# fms_controller.net
KiCad netlist of a schematic drawn in EAGLE
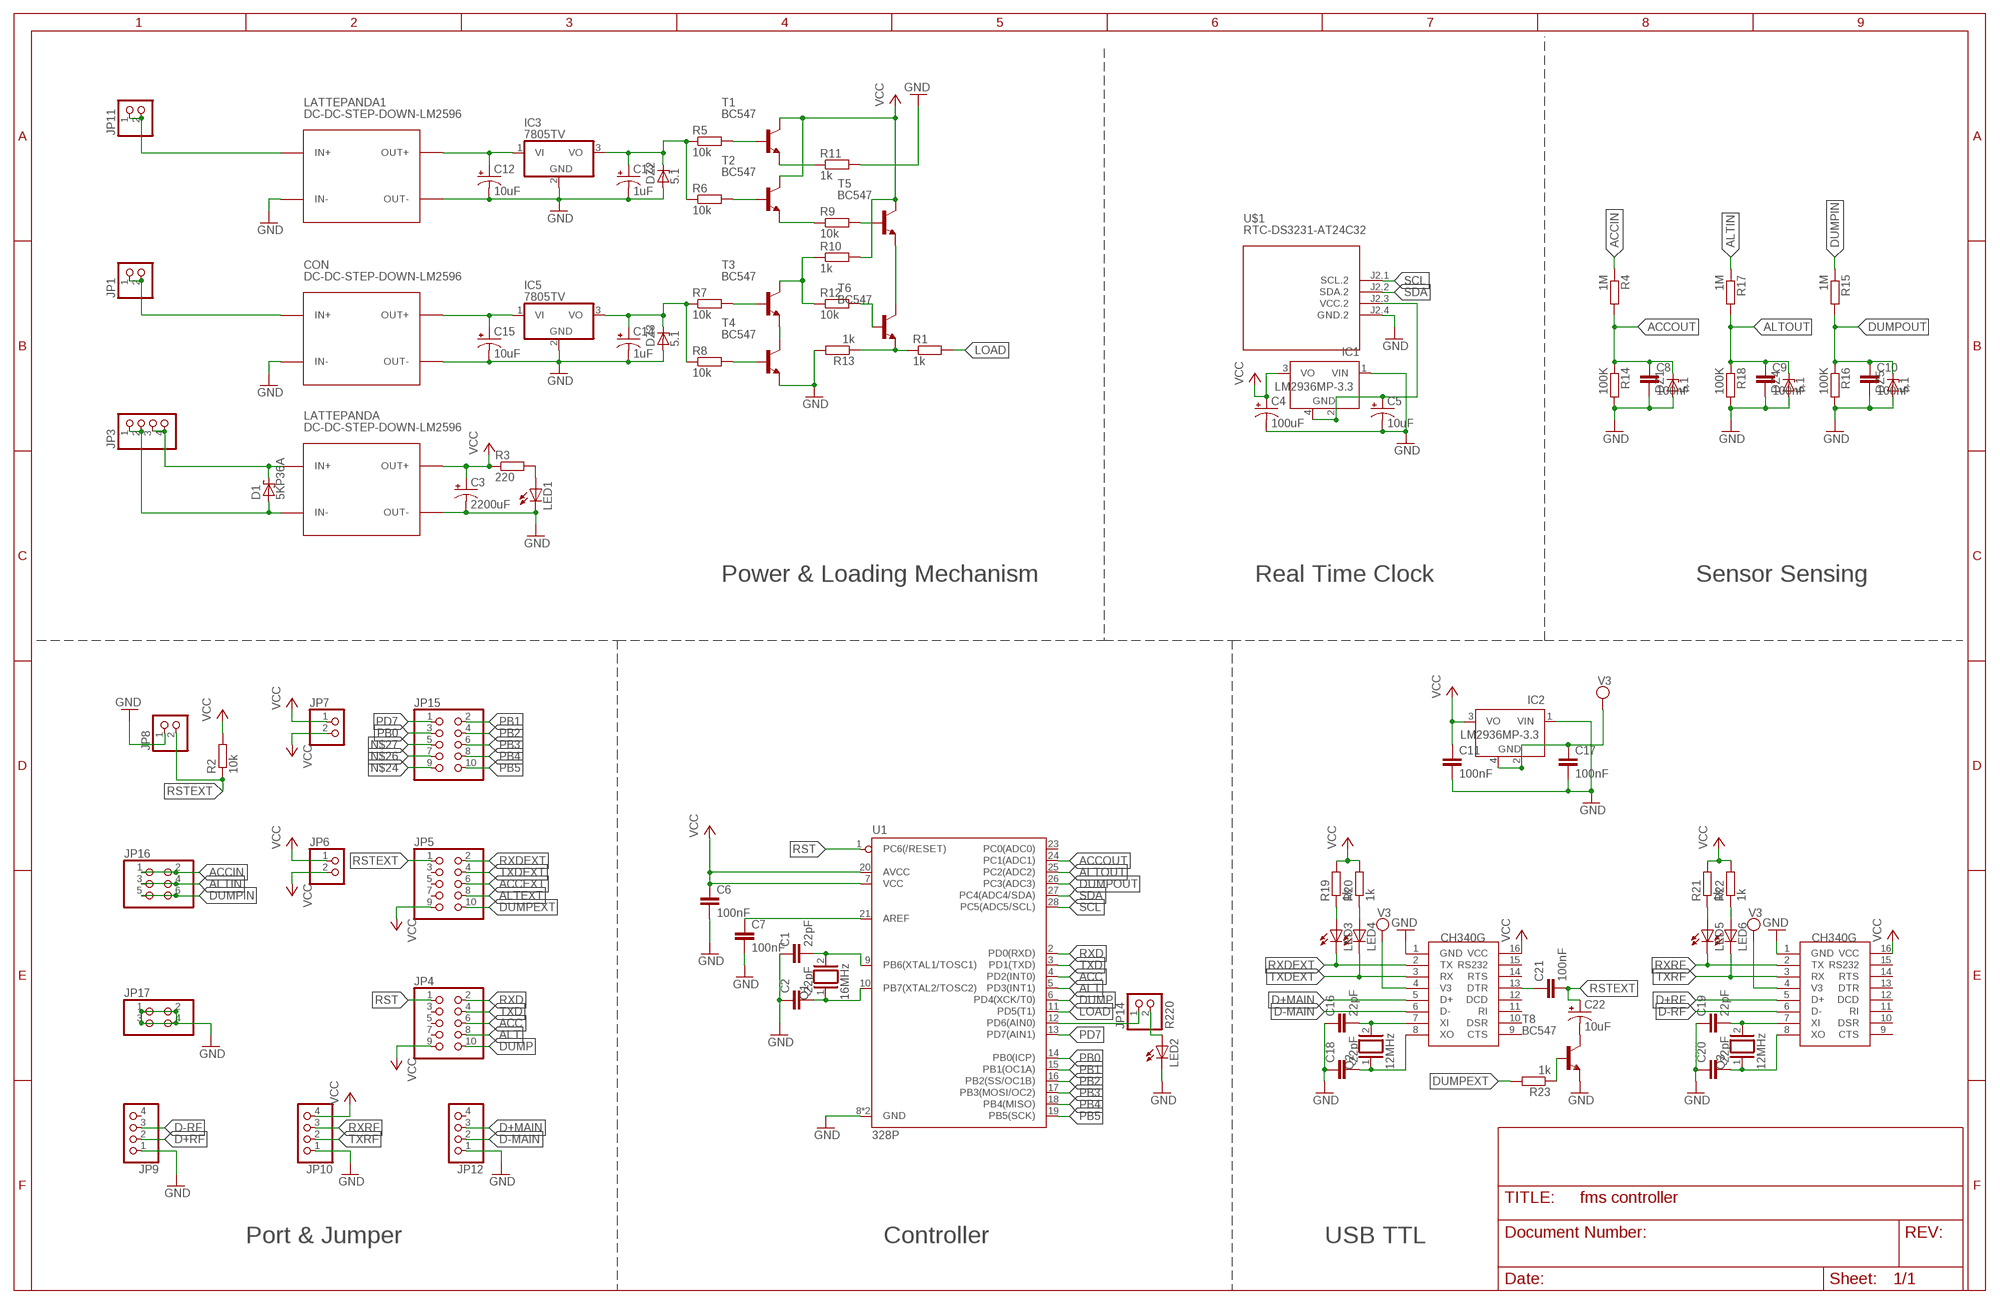
[diagram p0: schematic, sheet 1]

(export (version "E")
  (design (tool "Eeschema 10.0.6"))
  (components
    (comp (ref "C1")
      (value "22pF")
      (footprint "eagle-import:C2.5-3")
      (libsource (lib "eagle-import") (part "C2,5-3"))
    )
    (comp (ref "C2")
      (value "22pF")
      (footprint "eagle-import:C2.5-3")
      (libsource (lib "eagle-import") (part "C2,5-3"))
    )
    (comp (ref "C3")
      (value "2200uF")
      (footprint "eagle-import:E5-13")
      (libsource (lib "eagle-import") (part "CPOL-USE5-13"))
    )
    (comp (ref "C4")
      (value "100uF")
      (footprint "eagle-import:E2-5")
      (libsource (lib "eagle-import") (part "CPOL-USE2-5"))
    )
    (comp (ref "C5")
      (value "10uF")
      (footprint "eagle-import:E2-5")
      (libsource (lib "eagle-import") (part "CPOL-USE2-5"))
    )
    (comp (ref "C6")
      (value "100nF")
      (footprint "eagle-import:C025-040X050")
      (libsource (lib "eagle-import") (part "C-EU025-040X050"))
    )
    (comp (ref "C7")
      (value "100nF")
      (footprint "eagle-import:C025-040X050")
      (libsource (lib "eagle-import") (part "C-EU025-040X050"))
    )
    (comp (ref "C8")
      (value "100nF")
      (footprint "eagle-import:C025-040X050")
      (libsource (lib "eagle-import") (part "C-EU025-040X050"))
    )
    (comp (ref "C9")
      (value "100nF")
      (footprint "eagle-import:C025-040X050")
      (libsource (lib "eagle-import") (part "C-EU025-040X050"))
    )
    (comp (ref "C10")
      (value "100nF")
      (footprint "eagle-import:C025-040X050")
      (libsource (lib "eagle-import") (part "C-EU025-040X050"))
    )
    (comp (ref "C11")
      (value "100nF")
      (footprint "eagle-import:C025-040X050")
      (libsource (lib "eagle-import") (part "C-EU025-040X050"))
    )
    (comp (ref "C12")
      (value "10uF")
      (footprint "eagle-import:E2-5")
      (libsource (lib "eagle-import") (part "CPOL-USE2-5"))
    )
    (comp (ref "C13")
      (value "1uF")
      (footprint "eagle-import:E2-5")
      (libsource (lib "eagle-import") (part "CPOL-USE2-5"))
    )
    (comp (ref "C14")
      (value "1uF")
      (footprint "eagle-import:E2-5")
      (libsource (lib "eagle-import") (part "CPOL-USE2-5"))
    )
    (comp (ref "C15")
      (value "10uF")
      (footprint "eagle-import:E2-5")
      (libsource (lib "eagle-import") (part "CPOL-USE2-5"))
    )
    (comp (ref "C16")
      (value "22pF")
      (footprint "eagle-import:C2.5-3")
      (libsource (lib "eagle-import") (part "C2,5-3"))
    )
    (comp (ref "C17")
      (value "100nF")
      (footprint "eagle-import:C025-040X050")
      (libsource (lib "eagle-import") (part "C-EU025-040X050"))
    )
    (comp (ref "C18")
      (value "22pF")
      (footprint "eagle-import:C2.5-3")
      (libsource (lib "eagle-import") (part "C2,5-3"))
    )
    (comp (ref "C19")
      (value "22pF")
      (footprint "eagle-import:C2.5-3")
      (libsource (lib "eagle-import") (part "C2,5-3"))
    )
    (comp (ref "C20")
      (value "22pF")
      (footprint "eagle-import:C2.5-3")
      (libsource (lib "eagle-import") (part "C2,5-3"))
    )
    (comp (ref "C21")
      (value "100nF")
      (footprint "eagle-import:C025-040X050")
      (libsource (lib "eagle-import") (part "C-EU025-040X050"))
    )
    (comp (ref "C22")
      (value "10uF")
      (footprint "eagle-import:E2-5")
      (libsource (lib "eagle-import") (part "CPOL-USE2-5"))
    )
    (comp (ref "CON")
      (value "DC-DC-STEP-DOWN-LM2596")
      (footprint "eagle-import:DC-DC-STEP-DOWN-LM2596")
      (libsource (lib "eagle-import") (part "DC-DC-STEP-DOWN-LM2596"))
    )
    (comp (ref "D1")
      (value "5KP36A")
      (footprint "eagle-import:P6T15")
      (libsource (lib "eagle-import") (part "5KPXX"))
    )
    (comp (ref "DZ1")
      (value "5.1")
      (footprint "eagle-import:DO35Z10")
      (libsource (lib "eagle-import") (part "ZPD"))
    )
    (comp (ref "DZ2")
      (value "5.1")
      (footprint "eagle-import:DO35Z10")
      (libsource (lib "eagle-import") (part "ZPD"))
    )
    (comp (ref "DZ3")
      (value "5.1")
      (footprint "eagle-import:DO35Z10")
      (libsource (lib "eagle-import") (part "ZPD"))
    )
    (comp (ref "DZ4")
      (value "5.1")
      (footprint "eagle-import:DO35Z10")
      (libsource (lib "eagle-import") (part "ZPD"))
    )
    (comp (ref "DZ5")
      (value "5.1")
      (footprint "eagle-import:DO35Z10")
      (libsource (lib "eagle-import") (part "ZPD"))
    )
    (comp (ref "IC1")
      (value "LM2936MP-3.3")
      (footprint "eagle-import:SOT223")
      (fields (field (name "MF") "NATIONAL SEMICONDUCTOR") (field (name "MPN") "LM2936MP-3.3/NOPB"))
      (libsource (lib "eagle-import") (part "LM2936MP?-3.3"))
    )
    (comp (ref "IC2")
      (value "LM2936MP-3.3")
      (footprint "eagle-import:SOT223")
      (fields (field (name "MF") "NATIONAL SEMICONDUCTOR") (field (name "MPN") "LM2936MP-3.3/NOPB"))
      (libsource (lib "eagle-import") (part "LM2936MP?-3.3"))
    )
    (comp (ref "IC3")
      (value "7805TV")
      (footprint "eagle-import:TO220V")
      (libsource (lib "eagle-import") (part "78TV05"))
    )
    (comp (ref "IC5")
      (value "7805TV")
      (footprint "eagle-import:TO220V")
      (libsource (lib "eagle-import") (part "78TV05"))
    )
    (comp (ref "JP1")
      (value "PINHD-1X2")
      (footprint "eagle-import:1X02")
      (libsource (lib "eagle-import") (part "PINHD-1X2"))
    )
    (comp (ref "JP3")
      (value "PINHD-1X4")
      (footprint "eagle-import:1X04")
      (libsource (lib "eagle-import") (part "PINHD-1X4"))
    )
    (comp (ref "JP4")
      (value "PINHD-2X5")
      (footprint "eagle-import:2X05")
      (libsource (lib "eagle-import") (part "PINHD-2X5"))
    )
    (comp (ref "JP5")
      (value "PINHD-2X5")
      (footprint "eagle-import:2X05")
      (libsource (lib "eagle-import") (part "PINHD-2X5"))
    )
    (comp (ref "JP6")
      (value "PINHD-1X2")
      (footprint "eagle-import:1X02")
      (libsource (lib "eagle-import") (part "PINHD-1X2"))
    )
    (comp (ref "JP7")
      (value "PINHD-1X2")
      (footprint "eagle-import:1X02")
      (libsource (lib "eagle-import") (part "PINHD-1X2"))
    )
    (comp (ref "JP8")
      (value "PINHD-1X2")
      (footprint "eagle-import:1X02")
      (libsource (lib "eagle-import") (part "PINHD-1X2"))
    )
    (comp (ref "JP9")
      (value "PINHD-1X4")
      (footprint "eagle-import:1X04")
      (libsource (lib "eagle-import") (part "PINHD-1X4"))
    )
    (comp (ref "JP10")
      (value "PINHD-1X4")
      (footprint "eagle-import:1X04")
      (libsource (lib "eagle-import") (part "PINHD-1X4"))
    )
    (comp (ref "JP11")
      (value "PINHD-1X2")
      (footprint "eagle-import:1X02")
      (libsource (lib "eagle-import") (part "PINHD-1X2"))
    )
    (comp (ref "JP12")
      (value "PINHD-1X4")
      (footprint "eagle-import:1X04")
      (libsource (lib "eagle-import") (part "PINHD-1X4"))
    )
    (comp (ref "JP14")
      (value "R220")
      (footprint "eagle-import:1X02")
      (libsource (lib "eagle-import") (part "PINHD-1X2"))
    )
    (comp (ref "JP15")
      (value "PINHD-2X5")
      (footprint "eagle-import:2X05")
      (libsource (lib "eagle-import") (part "PINHD-2X5"))
    )
    (comp (ref "JP16")
      (value "PINHD-2X3")
      (footprint "eagle-import:2X03")
      (libsource (lib "eagle-import") (part "PINHD-2X3"))
    )
    (comp (ref "JP17")
      (value "PINHD-2X2")
      (footprint "eagle-import:2X02")
      (libsource (lib "eagle-import") (part "PINHD-2X2"))
    )
    (comp (ref "LATTEPANDA")
      (value "DC-DC-STEP-DOWN-LM2596")
      (footprint "eagle-import:DC-DC-STEP-DOWN-LM2596")
      (libsource (lib "eagle-import") (part "DC-DC-STEP-DOWN-LM2596"))
    )
    (comp (ref "LATTEPANDA1")
      (value "DC-DC-STEP-DOWN-LM2596")
      (footprint "eagle-import:DC-DC-STEP-DOWN-LM2596")
      (libsource (lib "eagle-import") (part "DC-DC-STEP-DOWN-LM2596"))
    )
    (comp (ref "LED1")
      (value "LED3MM")
      (footprint "eagle-import:LED3MM")
      (libsource (lib "eagle-import") (part "LED3MM"))
    )
    (comp (ref "LED2")
      (value "LED3MM")
      (footprint "eagle-import:LED3MM")
      (libsource (lib "eagle-import") (part "LED3MM"))
    )
    (comp (ref "LED3")
      (value "LED3MM")
      (footprint "eagle-import:LED3MM")
      (libsource (lib "eagle-import") (part "LED3MM"))
    )
    (comp (ref "LED4")
      (value "LED3MM")
      (footprint "eagle-import:LED3MM")
      (libsource (lib "eagle-import") (part "LED3MM"))
    )
    (comp (ref "LED5")
      (value "LED3MM")
      (footprint "eagle-import:LED3MM")
      (libsource (lib "eagle-import") (part "LED3MM"))
    )
    (comp (ref "LED6")
      (value "LED3MM")
      (footprint "eagle-import:LED3MM")
      (libsource (lib "eagle-import") (part "LED3MM"))
    )
    (comp (ref "Q1")
      (value "16MHz")
      (footprint "eagle-import:QS")
      (libsource (lib "eagle-import") (part "XTAL/S"))
    )
    (comp (ref "Q2")
      (value "12MHz")
      (footprint "eagle-import:QS")
      (libsource (lib "eagle-import") (part "XTAL/S"))
    )
    (comp (ref "Q3")
      (value "12MHz")
      (footprint "eagle-import:QS")
      (libsource (lib "eagle-import") (part "XTAL/S"))
    )
    (comp (ref "R1")
      (value "1k")
      (footprint "eagle-import:0309_10")
      (libsource (lib "eagle-import") (part "R-EU_0309/10"))
    )
    (comp (ref "R2")
      (value "10k")
      (footprint "eagle-import:0309_10")
      (libsource (lib "eagle-import") (part "R-EU_0309/10"))
    )
    (comp (ref "R3")
      (value "220")
      (footprint "eagle-import:0309_10")
      (libsource (lib "eagle-import") (part "R-EU_0309/10"))
    )
    (comp (ref "R4")
      (value "1M")
      (footprint "eagle-import:0309_10")
      (libsource (lib "eagle-import") (part "R-EU_0309/10"))
    )
    (comp (ref "R5")
      (value "10k")
      (footprint "eagle-import:0309_10")
      (libsource (lib "eagle-import") (part "R-EU_0309/10"))
    )
    (comp (ref "R6")
      (value "10k")
      (footprint "eagle-import:0309_10")
      (libsource (lib "eagle-import") (part "R-EU_0309/10"))
    )
    (comp (ref "R7")
      (value "10k")
      (footprint "eagle-import:0309_10")
      (libsource (lib "eagle-import") (part "R-EU_0309/10"))
    )
    (comp (ref "R8")
      (value "10k")
      (footprint "eagle-import:0309_10")
      (libsource (lib "eagle-import") (part "R-EU_0309/10"))
    )
    (comp (ref "R9")
      (value "10k")
      (footprint "eagle-import:0309_10")
      (libsource (lib "eagle-import") (part "R-EU_0309/10"))
    )
    (comp (ref "R10")
      (value "1k")
      (footprint "eagle-import:0309_10")
      (libsource (lib "eagle-import") (part "R-EU_0309/10"))
    )
    (comp (ref "R11")
      (value "1k")
      (footprint "eagle-import:0309_10")
      (libsource (lib "eagle-import") (part "R-EU_0309/10"))
    )
    (comp (ref "R12")
      (value "10k")
      (footprint "eagle-import:0309_10")
      (libsource (lib "eagle-import") (part "R-EU_0309/10"))
    )
    (comp (ref "R13")
      (value "1k")
      (footprint "eagle-import:0309_10")
      (libsource (lib "eagle-import") (part "R-EU_0309/10"))
    )
    (comp (ref "R14")
      (value "100K")
      (footprint "eagle-import:0309_10")
      (libsource (lib "eagle-import") (part "R-EU_0309/10"))
    )
    (comp (ref "R15")
      (value "1M")
      (footprint "eagle-import:0309_10")
      (libsource (lib "eagle-import") (part "R-EU_0309/10"))
    )
    (comp (ref "R16")
      (value "100K")
      (footprint "eagle-import:0309_10")
      (libsource (lib "eagle-import") (part "R-EU_0309/10"))
    )
    (comp (ref "R17")
      (value "1M")
      (footprint "eagle-import:0309_10")
      (libsource (lib "eagle-import") (part "R-EU_0309/10"))
    )
    (comp (ref "R18")
      (value "100K")
      (footprint "eagle-import:0309_10")
      (libsource (lib "eagle-import") (part "R-EU_0309/10"))
    )
    (comp (ref "R19")
      (value "1k")
      (footprint "eagle-import:0309_10")
      (libsource (lib "eagle-import") (part "R-EU_0309/10"))
    )
    (comp (ref "R20")
      (value "1k")
      (footprint "eagle-import:0309_10")
      (libsource (lib "eagle-import") (part "R-EU_0309/10"))
    )
    (comp (ref "R21")
      (value "1k")
      (footprint "eagle-import:0309_10")
      (libsource (lib "eagle-import") (part "R-EU_0309/10"))
    )
    (comp (ref "R22")
      (value "1k")
      (footprint "eagle-import:0309_10")
      (libsource (lib "eagle-import") (part "R-EU_0309/10"))
    )
    (comp (ref "R23")
      (value "1k")
      (footprint "eagle-import:0309_10")
      (libsource (lib "eagle-import") (part "R-EU_0309/10"))
    )
    (comp (ref "T1")
      (value "BC547")
      (footprint "eagle-import:TO92")
      (libsource (lib "eagle-import") (part "BC547"))
    )
    (comp (ref "T2")
      (value "BC547")
      (footprint "eagle-import:TO92")
      (libsource (lib "eagle-import") (part "BC547"))
    )
    (comp (ref "T3")
      (value "BC547")
      (footprint "eagle-import:TO92")
      (libsource (lib "eagle-import") (part "BC547"))
    )
    (comp (ref "T4")
      (value "BC547")
      (footprint "eagle-import:TO92")
      (libsource (lib "eagle-import") (part "BC547"))
    )
    (comp (ref "T5")
      (value "BC547")
      (footprint "eagle-import:TO92")
      (libsource (lib "eagle-import") (part "BC547"))
    )
    (comp (ref "T6")
      (value "BC547")
      (footprint "eagle-import:TO92")
      (libsource (lib "eagle-import") (part "BC547"))
    )
    (comp (ref "T8")
      (value "BC547")
      (footprint "eagle-import:TO92")
      (libsource (lib "eagle-import") (part "BC547"))
    )
    (comp (ref "U$1")
      (value "RTC-DS3231-AT24C32")
      (footprint "eagle-import:RTC-DS3231-AT24C32")
      (libsource (lib "eagle-import") (part "RTC-DS3231-AT24C32"))
    )
    (comp (ref "U$2")
      (value "CH340G")
      (footprint "eagle-import:SOIC16")
      (libsource (lib "eagle-import") (part "CH340G"))
    )
    (comp (ref "U$3")
      (value "CH340G")
      (footprint "eagle-import:SOIC16")
      (libsource (lib "eagle-import") (part "CH340G"))
    )
    (comp (ref "U1")
      (value "328P")
      (footprint "eagle-import:DIP28")
      (libsource (lib "eagle-import") (part "ATMEGA328P_PDIP"))
    )
  )
  (nets
    (net (code "1") (name "ACC") (class "Default")
      (node (ref "JP4") (pin "6") (pinfunction "6_6") (pintype "passive"))
      (node (ref "U1") (pin "4") (pinfunction "PD2(INT0)_4") (pintype "bidirectional"))
    )
    (net (code "2") (name "ACCEXT") (class "Default")
      (node (ref "JP5") (pin "6") (pinfunction "6_6") (pintype "passive"))
    )
    (net (code "3") (name "ACCIN") (class "Default")
      (node (ref "JP16") (pin "1") (pinfunction "1_1") (pintype "passive"))
      (node (ref "JP16") (pin "2") (pinfunction "2_2") (pintype "passive"))
      (node (ref "R4") (pin "1") (pinfunction "1_1") (pintype "passive"))
    )
    (net (code "4") (name "ACCOUT") (class "Default")
      (node (ref "C8") (pin "1") (pinfunction "1_1") (pintype "passive"))
      (node (ref "DZ1") (pin "C") (pinfunction "C_C") (pintype "passive"))
      (node (ref "R14") (pin "1") (pinfunction "1_1") (pintype "passive"))
      (node (ref "R4") (pin "2") (pinfunction "2_2") (pintype "passive"))
      (node (ref "U1") (pin "24") (pinfunction "PC1(ADC1)_24") (pintype "bidirectional"))
    )
    (net (code "5") (name "ALT") (class "Default")
      (node (ref "JP4") (pin "8") (pinfunction "8_8") (pintype "passive"))
      (node (ref "U1") (pin "5") (pinfunction "PD3(INT1)_5") (pintype "bidirectional"))
    )
    (net (code "6") (name "ALTEXT") (class "Default")
      (node (ref "JP5") (pin "8") (pinfunction "8_8") (pintype "passive"))
    )
    (net (code "7") (name "ALTIN") (class "Default")
      (node (ref "JP16") (pin "3") (pinfunction "3_3") (pintype "passive"))
      (node (ref "JP16") (pin "4") (pinfunction "4_4") (pintype "passive"))
      (node (ref "R17") (pin "1") (pinfunction "1_1") (pintype "passive"))
    )
    (net (code "8") (name "ALTOUT") (class "Default")
      (node (ref "C9") (pin "1") (pinfunction "1_1") (pintype "passive"))
      (node (ref "DZ4") (pin "C") (pinfunction "C_C") (pintype "passive"))
      (node (ref "R17") (pin "2") (pinfunction "2_2") (pintype "passive"))
      (node (ref "R18") (pin "1") (pinfunction "1_1") (pintype "passive"))
      (node (ref "U1") (pin "25") (pinfunction "PC2(ADC2)_25") (pintype "bidirectional"))
    )
    (net (code "9") (name "D+MAIN") (class "Default")
      (node (ref "JP12") (pin "3") (pinfunction "3_3") (pintype "passive"))
      (node (ref "U$2") (pin "5") (pinfunction "D+_5") (pintype "bidirectional"))
    )
    (net (code "10") (name "D+RF") (class "Default")
      (node (ref "JP9") (pin "2") (pinfunction "2_2") (pintype "passive"))
      (node (ref "U$3") (pin "5") (pinfunction "D+_5") (pintype "bidirectional"))
    )
    (net (code "11") (name "D-MAIN") (class "Default")
      (node (ref "JP12") (pin "2") (pinfunction "2_2") (pintype "passive"))
      (node (ref "U$2") (pin "6") (pinfunction "D-_6") (pintype "bidirectional"))
    )
    (net (code "12") (name "D-RF") (class "Default")
      (node (ref "JP9") (pin "3") (pinfunction "3_3") (pintype "passive"))
      (node (ref "U$3") (pin "6") (pinfunction "D-_6") (pintype "bidirectional"))
    )
    (net (code "13") (name "DUMP") (class "Default")
      (node (ref "JP4") (pin "10") (pinfunction "10_10") (pintype "passive"))
      (node (ref "U1") (pin "6") (pinfunction "PD4(XCK/T0)_6") (pintype "bidirectional"))
    )
    (net (code "14") (name "DUMPEXT") (class "Default")
      (node (ref "JP5") (pin "10") (pinfunction "10_10") (pintype "passive"))
      (node (ref "R23") (pin "2") (pinfunction "2_2") (pintype "passive"))
    )
    (net (code "15") (name "DUMPIN") (class "Default")
      (node (ref "JP16") (pin "5") (pinfunction "5_5") (pintype "passive"))
      (node (ref "JP16") (pin "6") (pinfunction "6_6") (pintype "passive"))
      (node (ref "R15") (pin "1") (pinfunction "1_1") (pintype "passive"))
    )
    (net (code "16") (name "DUMPOUT") (class "Default")
      (node (ref "C10") (pin "1") (pinfunction "1_1") (pintype "passive"))
      (node (ref "DZ5") (pin "C") (pinfunction "C_C") (pintype "passive"))
      (node (ref "R15") (pin "2") (pinfunction "2_2") (pintype "passive"))
      (node (ref "R16") (pin "1") (pinfunction "1_1") (pintype "passive"))
      (node (ref "U1") (pin "26") (pinfunction "PC3(ADC3)_26") (pintype "bidirectional"))
    )
    (net (code "17") (name "GND") (class "Default")
      (node (ref "C1") (pin "1") (pinfunction "1_1") (pintype "passive"))
      (node (ref "C10") (pin "2") (pinfunction "2_2") (pintype "passive"))
      (node (ref "C11") (pin "2") (pinfunction "2_2") (pintype "passive"))
      (node (ref "C12") (pin "-") (pinfunction "-_-") (pintype "passive"))
      (node (ref "C13") (pin "-") (pinfunction "-_-") (pintype "passive"))
      (node (ref "C14") (pin "-") (pinfunction "-_-") (pintype "passive"))
      (node (ref "C15") (pin "-") (pinfunction "-_-") (pintype "passive"))
      (node (ref "C16") (pin "1") (pinfunction "1_1") (pintype "passive"))
      (node (ref "C17") (pin "2") (pinfunction "2_2") (pintype "passive"))
      (node (ref "C18") (pin "1") (pinfunction "1_1") (pintype "passive"))
      (node (ref "C19") (pin "1") (pinfunction "1_1") (pintype "passive"))
      (node (ref "C2") (pin "1") (pinfunction "1_1") (pintype "passive"))
      (node (ref "C20") (pin "1") (pinfunction "1_1") (pintype "passive"))
      (node (ref "C3") (pin "-") (pinfunction "-_-") (pintype "passive"))
      (node (ref "C4") (pin "-") (pinfunction "-_-") (pintype "passive"))
      (node (ref "C5") (pin "-") (pinfunction "-_-") (pintype "passive"))
      (node (ref "C6") (pin "2") (pinfunction "2_2") (pintype "passive"))
      (node (ref "C7") (pin "2") (pinfunction "2_2") (pintype "passive"))
      (node (ref "C8") (pin "2") (pinfunction "2_2") (pintype "passive"))
      (node (ref "C9") (pin "2") (pinfunction "2_2") (pintype "passive"))
      (node (ref "CON") (pin "IN-") (pinfunction "IN-_IN-") (pintype "bidirectional"))
      (node (ref "CON") (pin "OUT-") (pinfunction "OUT-_OUT-") (pintype "bidirectional"))
      (node (ref "DZ1") (pin "A") (pinfunction "A_A") (pintype "passive"))
      (node (ref "DZ2") (pin "A") (pinfunction "A_A") (pintype "passive"))
      (node (ref "DZ3") (pin "A") (pinfunction "A_A") (pintype "passive"))
      (node (ref "DZ4") (pin "A") (pinfunction "A_A") (pintype "passive"))
      (node (ref "DZ5") (pin "A") (pinfunction "A_A") (pintype "passive"))
      (node (ref "IC1") (pin "1") (pinfunction "VIN_1") (pintype "input"))
      (node (ref "IC2") (pin "1") (pinfunction "VIN_1") (pintype "input"))
      (node (ref "IC3") (pin "2") (pinfunction "GND_2") (pintype "passive"))
      (node (ref "IC5") (pin "2") (pinfunction "GND_2") (pintype "passive"))
      (node (ref "JP10") (pin "1") (pinfunction "1_1") (pintype "passive"))
      (node (ref "JP12") (pin "1") (pinfunction "1_1") (pintype "passive"))
      (node (ref "JP17") (pin "1") (pinfunction "1_1") (pintype "passive"))
      (node (ref "JP17") (pin "2") (pinfunction "2_2") (pintype "passive"))
      (node (ref "JP17") (pin "3") (pinfunction "3_3") (pintype "passive"))
      (node (ref "JP17") (pin "4") (pinfunction "4_4") (pintype "passive"))
      (node (ref "JP8") (pin "1") (pinfunction "1_1") (pintype "passive"))
      (node (ref "JP9") (pin "1") (pinfunction "1_1") (pintype "passive"))
      (node (ref "LATTEPANDA") (pin "OUT-") (pinfunction "OUT-_OUT-") (pintype "bidirectional"))
      (node (ref "LATTEPANDA1") (pin "IN-") (pinfunction "IN-_IN-") (pintype "bidirectional"))
      (node (ref "LATTEPANDA1") (pin "OUT-") (pinfunction "OUT-_OUT-") (pintype "bidirectional"))
      (node (ref "LED1") (pin "K") (pinfunction "C_K") (pintype "passive"))
      (node (ref "LED2") (pin "K") (pinfunction "C_K") (pintype "passive"))
      (node (ref "R11") (pin "2") (pinfunction "2_2") (pintype "passive"))
      (node (ref "R13") (pin "2") (pinfunction "2_2") (pintype "passive"))
      (node (ref "R14") (pin "2") (pinfunction "2_2") (pintype "passive"))
      (node (ref "R16") (pin "2") (pinfunction "2_2") (pintype "passive"))
      (node (ref "R18") (pin "2") (pinfunction "2_2") (pintype "passive"))
      (node (ref "T4") (pin "1") (pinfunction "E_1") (pintype "passive"))
      (node (ref "T8") (pin "1") (pinfunction "E_1") (pintype "passive"))
      (node (ref "U$1") (pin "J2.4") (pinfunction "GND.2_J2.4") (pintype "power_in"))
      (node (ref "U$2") (pin "1") (pinfunction "GND_1") (pintype "bidirectional"))
      (node (ref "U$3") (pin "1") (pinfunction "GND_1") (pintype "bidirectional"))
      (node (ref "U1") (pin "22") (pinfunction "GND_22") (pintype "bidirectional"))
      (node (ref "U1") (pin "8") (pinfunction "GND_8") (pintype "bidirectional"))
    )
    (net (code "18") (name "LOAD") (class "Default")
      (node (ref "R1") (pin "2") (pinfunction "2_2") (pintype "passive"))
      (node (ref "U1") (pin "11") (pinfunction "PD5(T1)_11") (pintype "bidirectional"))
    )
    (net (code "19") (name "N$24") (class "Default")
      (node (ref "JP15") (pin "9") (pinfunction "9_9") (pintype "passive"))
    )
    (net (code "20") (name "N$26") (class "Default")
      (node (ref "JP15") (pin "7") (pinfunction "7_7") (pintype "passive"))
    )
    (net (code "21") (name "N$27") (class "Default")
      (node (ref "JP15") (pin "5") (pinfunction "5_5") (pintype "passive"))
    )
    (net (code "22") (name "Net-(CON-PadIN+)") (class "Default")
      (node (ref "CON") (pin "IN+") (pinfunction "IN+_IN+") (pintype "bidirectional"))
      (node (ref "JP1") (pin "1") (pinfunction "1_1") (pintype "passive"))
      (node (ref "JP1") (pin "2") (pinfunction "2_2") (pintype "passive"))
    )
    (net (code "23") (name "Net-(D1-PadA)") (class "Default")
      (node (ref "D1") (pin "A") (pinfunction "A_A") (pintype "passive"))
      (node (ref "JP3") (pin "1") (pinfunction "1_1") (pintype "passive"))
      (node (ref "JP3") (pin "2") (pinfunction "2_2") (pintype "passive"))
      (node (ref "LATTEPANDA") (pin "IN-") (pinfunction "IN-_IN-") (pintype "bidirectional"))
    )
    (net (code "24") (name "Net-(D1-PadC)") (class "Default")
      (node (ref "D1") (pin "C") (pinfunction "C_C") (pintype "passive"))
      (node (ref "JP3") (pin "3") (pinfunction "3_3") (pintype "passive"))
      (node (ref "JP3") (pin "4") (pinfunction "4_4") (pintype "passive"))
      (node (ref "LATTEPANDA") (pin "IN+") (pinfunction "IN+_IN+") (pintype "bidirectional"))
    )
    (net (code "25") (name "Net-(IC3-VI)") (class "Default")
      (node (ref "C12") (pin "+") (pinfunction "+_+") (pintype "passive"))
      (node (ref "IC3") (pin "1") (pinfunction "VI_1") (pintype "input"))
      (node (ref "LATTEPANDA1") (pin "OUT+") (pinfunction "OUT+_OUT+") (pintype "bidirectional"))
    )
    (net (code "26") (name "Net-(IC3-VO)") (class "Default")
      (node (ref "C13") (pin "+") (pinfunction "+_+") (pintype "passive"))
      (node (ref "DZ2") (pin "C") (pinfunction "C_C") (pintype "passive"))
      (node (ref "IC3") (pin "3") (pinfunction "VO_3") (pintype "passive"))
      (node (ref "R5") (pin "1") (pinfunction "1_1") (pintype "passive"))
      (node (ref "R6") (pin "1") (pinfunction "1_1") (pintype "passive"))
    )
    (net (code "27") (name "Net-(IC5-VI)") (class "Default")
      (node (ref "C15") (pin "+") (pinfunction "+_+") (pintype "passive"))
      (node (ref "CON") (pin "OUT+") (pinfunction "OUT+_OUT+") (pintype "bidirectional"))
      (node (ref "IC5") (pin "1") (pinfunction "VI_1") (pintype "input"))
    )
    (net (code "28") (name "Net-(IC5-VO)") (class "Default")
      (node (ref "C14") (pin "+") (pinfunction "+_+") (pintype "passive"))
      (node (ref "DZ3") (pin "C") (pinfunction "C_C") (pintype "passive"))
      (node (ref "IC5") (pin "3") (pinfunction "VO_3") (pintype "passive"))
      (node (ref "R7") (pin "1") (pinfunction "1_1") (pintype "passive"))
      (node (ref "R8") (pin "1") (pinfunction "1_1") (pintype "passive"))
    )
    (net (code "29") (name "Net-(JP11-Pad1)") (class "Default")
      (node (ref "JP11") (pin "1") (pinfunction "1_1") (pintype "passive"))
      (node (ref "JP11") (pin "2") (pinfunction "2_2") (pintype "passive"))
      (node (ref "LATTEPANDA1") (pin "IN+") (pinfunction "IN+_IN+") (pintype "bidirectional"))
    )
    (net (code "30") (name "Net-(JP14-Pad2)") (class "Default")
      (node (ref "JP14") (pin "2") (pinfunction "2_2") (pintype "passive"))
      (node (ref "LED2") (pin "A") (pinfunction "A_A") (pintype "passive"))
    )
    (net (code "31") (name "Net-(LED1-PadA)") (class "Default")
      (node (ref "LED1") (pin "A") (pinfunction "A_A") (pintype "passive"))
      (node (ref "R3") (pin "2") (pinfunction "2_2") (pintype "passive"))
    )
    (net (code "32") (name "Net-(LED3-PadA)") (class "Default")
      (node (ref "LED3") (pin "A") (pinfunction "A_A") (pintype "passive"))
      (node (ref "R19") (pin "1") (pinfunction "1_1") (pintype "passive"))
    )
    (net (code "33") (name "Net-(LED4-PadA)") (class "Default")
      (node (ref "LED4") (pin "A") (pinfunction "A_A") (pintype "passive"))
      (node (ref "R20") (pin "1") (pinfunction "1_1") (pintype "passive"))
    )
    (net (code "34") (name "Net-(LED5-PadA)") (class "Default")
      (node (ref "LED5") (pin "A") (pinfunction "A_A") (pintype "passive"))
      (node (ref "R21") (pin "1") (pinfunction "1_1") (pintype "passive"))
    )
    (net (code "35") (name "Net-(LED6-PadA)") (class "Default")
      (node (ref "LED6") (pin "A") (pinfunction "A_A") (pintype "passive"))
      (node (ref "R22") (pin "1") (pinfunction "1_1") (pintype "passive"))
    )
    (net (code "36") (name "Net-(T1-B)") (class "Default")
      (node (ref "R5") (pin "2") (pinfunction "2_2") (pintype "passive"))
      (node (ref "T1") (pin "2") (pinfunction "B_2") (pintype "passive"))
    )
    (net (code "37") (name "Net-(T1-E)") (class "Default")
      (node (ref "R11") (pin "1") (pinfunction "1_1") (pintype "passive"))
      (node (ref "T1") (pin "1") (pinfunction "E_1") (pintype "passive"))
    )
    (net (code "38") (name "Net-(T2-B)") (class "Default")
      (node (ref "R6") (pin "2") (pinfunction "2_2") (pintype "passive"))
      (node (ref "T2") (pin "2") (pinfunction "B_2") (pintype "passive"))
    )
    (net (code "39") (name "Net-(T2-E)") (class "Default")
      (node (ref "R9") (pin "1") (pinfunction "1_1") (pintype "passive"))
      (node (ref "T2") (pin "1") (pinfunction "E_1") (pintype "passive"))
    )
    (net (code "40") (name "Net-(T3-B)") (class "Default")
      (node (ref "R7") (pin "2") (pinfunction "2_2") (pintype "passive"))
      (node (ref "T3") (pin "2") (pinfunction "B_2") (pintype "passive"))
    )
    (net (code "41") (name "Net-(T3-C)") (class "Default")
      (node (ref "R10") (pin "1") (pinfunction "1_1") (pintype "passive"))
      (node (ref "R12") (pin "1") (pinfunction "1_1") (pintype "passive"))
      (node (ref "T3") (pin "3") (pinfunction "C_3") (pintype "passive"))
    )
    (net (code "42") (name "Net-(T3-E)") (class "Default")
      (node (ref "T3") (pin "1") (pinfunction "E_1") (pintype "passive"))
      (node (ref "T4") (pin "3") (pinfunction "C_3") (pintype "passive"))
    )
    (net (code "43") (name "Net-(T4-B)") (class "Default")
      (node (ref "R8") (pin "2") (pinfunction "2_2") (pintype "passive"))
      (node (ref "T4") (pin "2") (pinfunction "B_2") (pintype "passive"))
    )
    (net (code "44") (name "Net-(T5-B)") (class "Default")
      (node (ref "R9") (pin "2") (pinfunction "2_2") (pintype "passive"))
      (node (ref "T5") (pin "2") (pinfunction "B_2") (pintype "passive"))
    )
    (net (code "45") (name "Net-(T5-E)") (class "Default")
      (node (ref "T5") (pin "1") (pinfunction "E_1") (pintype "passive"))
      (node (ref "T6") (pin "3") (pinfunction "C_3") (pintype "passive"))
    )
    (net (code "46") (name "Net-(T6-B)") (class "Default")
      (node (ref "R12") (pin "2") (pinfunction "2_2") (pintype "passive"))
      (node (ref "T6") (pin "2") (pinfunction "B_2") (pintype "passive"))
    )
    (net (code "47") (name "Net-(T6-E)") (class "Default")
      (node (ref "R1") (pin "1") (pinfunction "1_1") (pintype "passive"))
      (node (ref "R13") (pin "1") (pinfunction "1_1") (pintype "passive"))
      (node (ref "T6") (pin "1") (pinfunction "E_1") (pintype "passive"))
    )
    (net (code "48") (name "Net-(T8-B)") (class "Default")
      (node (ref "R23") (pin "1") (pinfunction "1_1") (pintype "passive"))
      (node (ref "T8") (pin "2") (pinfunction "B_2") (pintype "passive"))
    )
    (net (code "49") (name "Net-(T8-C)") (class "Default")
      (node (ref "C22") (pin "-") (pinfunction "-_-") (pintype "passive"))
      (node (ref "T8") (pin "3") (pinfunction "C_3") (pintype "passive"))
    )
    (net (code "50") (name "Net-(U$1-VCC.2)") (class "Default")
      (node (ref "C5") (pin "+") (pinfunction "+_+") (pintype "passive"))
      (node (ref "IC1") (pin "2") (pinfunction "GND_2") (pintype "passive"))
      (node (ref "IC1") (pin "4") (pinfunction "GND_4") (pintype "passive"))
      (node (ref "U$1") (pin "J2.3") (pinfunction "VCC.2_J2.3") (pintype "power_in"))
    )
    (net (code "51") (name "Net-(U$2-DTR)") (class "Default")
      (node (ref "C21") (pin "1") (pinfunction "1_1") (pintype "passive"))
      (node (ref "U$2") (pin "13") (pinfunction "DTR_13") (pintype "bidirectional"))
    )
    (net (code "52") (name "Net-(U$2-XI)") (class "Default")
      (node (ref "C16") (pin "2") (pinfunction "2_2") (pintype "passive"))
      (node (ref "Q2") (pin "2") (pinfunction "2_2") (pintype "passive"))
      (node (ref "U$2") (pin "7") (pinfunction "XI_7") (pintype "bidirectional"))
    )
    (net (code "53") (name "Net-(U$2-XO)") (class "Default")
      (node (ref "C18") (pin "2") (pinfunction "2_2") (pintype "passive"))
      (node (ref "Q2") (pin "1") (pinfunction "1_1") (pintype "passive"))
      (node (ref "U$2") (pin "8") (pinfunction "XO_8") (pintype "bidirectional"))
    )
    (net (code "54") (name "Net-(U$3-XI)") (class "Default")
      (node (ref "C19") (pin "2") (pinfunction "2_2") (pintype "passive"))
      (node (ref "Q3") (pin "2") (pinfunction "2_2") (pintype "passive"))
      (node (ref "U$3") (pin "7") (pinfunction "XI_7") (pintype "bidirectional"))
    )
    (net (code "55") (name "Net-(U$3-XO)") (class "Default")
      (node (ref "C20") (pin "2") (pinfunction "2_2") (pintype "passive"))
      (node (ref "Q3") (pin "1") (pinfunction "1_1") (pintype "passive"))
      (node (ref "U$3") (pin "8") (pinfunction "XO_8") (pintype "bidirectional"))
    )
    (net (code "56") (name "Net-(U1-AREF)") (class "Default")
      (node (ref "C7") (pin "1") (pinfunction "1_1") (pintype "passive"))
      (node (ref "U1") (pin "21") (pinfunction "AREF_21") (pintype "bidirectional"))
    )
    (net (code "57") (name "Net-(U1-PB6(XTAL1{slash}TOSC1))") (class "Default")
      (node (ref "C1") (pin "2") (pinfunction "2_2") (pintype "passive"))
      (node (ref "Q1") (pin "2") (pinfunction "2_2") (pintype "passive"))
      (node (ref "U1") (pin "9") (pinfunction "PB6(XTAL1/TOSC1)_9") (pintype "bidirectional"))
    )
    (net (code "58") (name "Net-(U1-PB7(XTAL2{slash}TOSC2))") (class "Default")
      (node (ref "C2") (pin "2") (pinfunction "2_2") (pintype "passive"))
      (node (ref "Q1") (pin "1") (pinfunction "1_1") (pintype "passive"))
      (node (ref "U1") (pin "10") (pinfunction "PB7(XTAL2/TOSC2)_10") (pintype "bidirectional"))
    )
    (net (code "59") (name "Net-(U1-PD6(AIN0))") (class "Default")
      (node (ref "JP14") (pin "1") (pinfunction "1_1") (pintype "passive"))
      (node (ref "U1") (pin "12") (pinfunction "PD6(AIN0)_12") (pintype "bidirectional"))
    )
    (net (code "60") (name "PB0") (class "Default")
      (node (ref "JP15") (pin "3") (pinfunction "3_3") (pintype "passive"))
      (node (ref "U1") (pin "14") (pinfunction "PB0(ICP)_14") (pintype "bidirectional"))
    )
    (net (code "61") (name "PB1") (class "Default")
      (node (ref "JP15") (pin "2") (pinfunction "2_2") (pintype "passive"))
      (node (ref "U1") (pin "15") (pinfunction "PB1(OC1A)_15") (pintype "bidirectional"))
    )
    (net (code "62") (name "PB2") (class "Default")
      (node (ref "JP15") (pin "4") (pinfunction "4_4") (pintype "passive"))
      (node (ref "U1") (pin "16") (pinfunction "PB2(SS/OC1B)_16") (pintype "bidirectional"))
    )
    (net (code "63") (name "PB3") (class "Default")
      (node (ref "JP15") (pin "6") (pinfunction "6_6") (pintype "passive"))
      (node (ref "U1") (pin "17") (pinfunction "PB3(MOSI/OC2)_17") (pintype "bidirectional"))
    )
    (net (code "64") (name "PB4") (class "Default")
      (node (ref "JP15") (pin "8") (pinfunction "8_8") (pintype "passive"))
      (node (ref "U1") (pin "18") (pinfunction "PB4(MISO)_18") (pintype "bidirectional"))
    )
    (net (code "65") (name "PB5") (class "Default")
      (node (ref "JP15") (pin "10") (pinfunction "10_10") (pintype "passive"))
      (node (ref "U1") (pin "19") (pinfunction "PB5(SCK)_19") (pintype "bidirectional"))
    )
    (net (code "66") (name "PD7") (class "Default")
      (node (ref "JP15") (pin "1") (pinfunction "1_1") (pintype "passive"))
      (node (ref "U1") (pin "13") (pinfunction "PD7(AIN1)_13") (pintype "bidirectional"))
    )
    (net (code "67") (name "RST") (class "Default")
      (node (ref "JP4") (pin "1") (pinfunction "1_1") (pintype "passive"))
      (node (ref "U1") (pin "1") (pinfunction "PC6(/RESET)_1") (pintype "bidirectional"))
    )
    (net (code "68") (name "RSTEXT") (class "Default")
      (node (ref "C21") (pin "2") (pinfunction "2_2") (pintype "passive"))
      (node (ref "C22") (pin "+") (pinfunction "+_+") (pintype "passive"))
      (node (ref "JP5") (pin "1") (pinfunction "1_1") (pintype "passive"))
      (node (ref "JP8") (pin "2") (pinfunction "2_2") (pintype "passive"))
      (node (ref "R2") (pin "1") (pinfunction "1_1") (pintype "passive"))
    )
    (net (code "69") (name "RXD") (class "Default")
      (node (ref "JP4") (pin "2") (pinfunction "2_2") (pintype "passive"))
      (node (ref "U1") (pin "2") (pinfunction "PD0(RXD)_2") (pintype "bidirectional"))
    )
    (net (code "70") (name "RXDEXT") (class "Default")
      (node (ref "JP5") (pin "2") (pinfunction "2_2") (pintype "passive"))
      (node (ref "LED3") (pin "K") (pinfunction "C_K") (pintype "passive"))
      (node (ref "U$2") (pin "2") (pinfunction "TX_2") (pintype "bidirectional"))
    )
    (net (code "71") (name "RXRF") (class "Default")
      (node (ref "JP10") (pin "3") (pinfunction "3_3") (pintype "passive"))
      (node (ref "LED5") (pin "K") (pinfunction "C_K") (pintype "passive"))
      (node (ref "U$3") (pin "2") (pinfunction "TX_2") (pintype "bidirectional"))
    )
    (net (code "72") (name "SCL") (class "Default")
      (node (ref "U$1") (pin "J2.1") (pinfunction "SCL.2_J2.1") (pintype "bidirectional"))
      (node (ref "U1") (pin "28") (pinfunction "PC5(ADC5/SCL)_28") (pintype "bidirectional"))
    )
    (net (code "73") (name "SDA") (class "Default")
      (node (ref "U$1") (pin "J2.2") (pinfunction "SDA.2_J2.2") (pintype "bidirectional"))
      (node (ref "U1") (pin "27") (pinfunction "PC4(ADC4/SDA)_27") (pintype "bidirectional"))
    )
    (net (code "74") (name "TXD") (class "Default")
      (node (ref "JP4") (pin "4") (pinfunction "4_4") (pintype "passive"))
      (node (ref "U1") (pin "3") (pinfunction "PD1(TXD)_3") (pintype "bidirectional"))
    )
    (net (code "75") (name "TXDEXT") (class "Default")
      (node (ref "JP5") (pin "4") (pinfunction "4_4") (pintype "passive"))
      (node (ref "LED4") (pin "K") (pinfunction "C_K") (pintype "passive"))
      (node (ref "U$2") (pin "3") (pinfunction "RX_3") (pintype "bidirectional"))
    )
    (net (code "76") (name "TXRF") (class "Default")
      (node (ref "JP10") (pin "2") (pinfunction "2_2") (pintype "passive"))
      (node (ref "LED6") (pin "K") (pinfunction "C_K") (pintype "passive"))
      (node (ref "U$3") (pin "3") (pinfunction "RX_3") (pintype "bidirectional"))
    )
    (net (code "77") (name "V3") (class "Default")
      (node (ref "C17") (pin "1") (pinfunction "1_1") (pintype "passive"))
      (node (ref "IC2") (pin "2") (pinfunction "GND_2") (pintype "passive"))
      (node (ref "IC2") (pin "4") (pinfunction "GND_4") (pintype "passive"))
      (node (ref "U$2") (pin "4") (pinfunction "V3_4") (pintype "bidirectional"))
      (node (ref "U$3") (pin "4") (pinfunction "V3_4") (pintype "bidirectional"))
    )
    (net (code "78") (name "VCC") (class "Default")
      (node (ref "C11") (pin "1") (pinfunction "1_1") (pintype "passive"))
      (node (ref "C3") (pin "+") (pinfunction "+_+") (pintype "passive"))
      (node (ref "C4") (pin "+") (pinfunction "+_+") (pintype "passive"))
      (node (ref "C6") (pin "1") (pinfunction "1_1") (pintype "passive"))
      (node (ref "IC1") (pin "3") (pinfunction "VO_3") (pintype "passive"))
      (node (ref "IC2") (pin "3") (pinfunction "VO_3") (pintype "passive"))
      (node (ref "JP10") (pin "4") (pinfunction "4_4") (pintype "passive"))
      (node (ref "JP4") (pin "9") (pinfunction "9_9") (pintype "passive"))
      (node (ref "JP5") (pin "9") (pinfunction "9_9") (pintype "passive"))
      (node (ref "JP6") (pin "1") (pinfunction "1_1") (pintype "passive"))
      (node (ref "JP6") (pin "2") (pinfunction "2_2") (pintype "passive"))
      (node (ref "JP7") (pin "1") (pinfunction "1_1") (pintype "passive"))
      (node (ref "JP7") (pin "2") (pinfunction "2_2") (pintype "passive"))
      (node (ref "LATTEPANDA") (pin "OUT+") (pinfunction "OUT+_OUT+") (pintype "bidirectional"))
      (node (ref "R10") (pin "2") (pinfunction "2_2") (pintype "passive"))
      (node (ref "R19") (pin "2") (pinfunction "2_2") (pintype "passive"))
      (node (ref "R2") (pin "2") (pinfunction "2_2") (pintype "passive"))
      (node (ref "R20") (pin "2") (pinfunction "2_2") (pintype "passive"))
      (node (ref "R21") (pin "2") (pinfunction "2_2") (pintype "passive"))
      (node (ref "R22") (pin "2") (pinfunction "2_2") (pintype "passive"))
      (node (ref "R3") (pin "1") (pinfunction "1_1") (pintype "passive"))
      (node (ref "T1") (pin "3") (pinfunction "C_3") (pintype "passive"))
      (node (ref "T2") (pin "3") (pinfunction "C_3") (pintype "passive"))
      (node (ref "T5") (pin "3") (pinfunction "C_3") (pintype "passive"))
      (node (ref "U$2") (pin "16") (pinfunction "VCC_16") (pintype "bidirectional"))
      (node (ref "U$3") (pin "16") (pinfunction "VCC_16") (pintype "bidirectional"))
      (node (ref "U1") (pin "20") (pinfunction "AVCC_20") (pintype "bidirectional"))
      (node (ref "U1") (pin "7") (pinfunction "VCC_7") (pintype "bidirectional"))
    )
    (net (code "79") (name "unconnected-(JP4-Pad3)") (class "Default")
      (node (ref "JP4") (pin "3") (pinfunction "3_3") (pintype "passive"))
    )
    (net (code "80") (name "unconnected-(JP4-Pad5)") (class "Default")
      (node (ref "JP4") (pin "5") (pinfunction "5_5") (pintype "passive"))
    )
    (net (code "81") (name "unconnected-(JP4-Pad7)") (class "Default")
      (node (ref "JP4") (pin "7") (pinfunction "7_7") (pintype "passive"))
    )
    (net (code "82") (name "unconnected-(JP5-Pad3)") (class "Default")
      (node (ref "JP5") (pin "3") (pinfunction "3_3") (pintype "passive"))
    )
    (net (code "83") (name "unconnected-(JP5-Pad5)") (class "Default")
      (node (ref "JP5") (pin "5") (pinfunction "5_5") (pintype "passive"))
    )
    (net (code "84") (name "unconnected-(JP5-Pad7)") (class "Default")
      (node (ref "JP5") (pin "7") (pinfunction "7_7") (pintype "passive"))
    )
    (net (code "85") (name "unconnected-(JP9-Pad4)") (class "Default")
      (node (ref "JP9") (pin "4") (pinfunction "4_4") (pintype "passive"))
    )
    (net (code "86") (name "unconnected-(JP12-Pad4)") (class "Default")
      (node (ref "JP12") (pin "4") (pinfunction "4_4") (pintype "passive"))
    )
    (net (code "87") (name "unconnected-(U$2-CTS-Pad9)") (class "Default")
      (node (ref "U$2") (pin "9") (pinfunction "CTS_9") (pintype "bidirectional"))
    )
    (net (code "88") (name "unconnected-(U$2-DCD-Pad12)") (class "Default")
      (node (ref "U$2") (pin "12") (pinfunction "DCD_12") (pintype "bidirectional"))
    )
    (net (code "89") (name "unconnected-(U$2-DSR-Pad10)") (class "Default")
      (node (ref "U$2") (pin "10") (pinfunction "DSR_10") (pintype "bidirectional"))
    )
    (net (code "90") (name "unconnected-(U$2-RI-Pad11)") (class "Default")
      (node (ref "U$2") (pin "11") (pinfunction "RI_11") (pintype "bidirectional"))
    )
    (net (code "91") (name "unconnected-(U$2-RS232-Pad15)") (class "Default")
      (node (ref "U$2") (pin "15") (pinfunction "RS232_15") (pintype "bidirectional"))
    )
    (net (code "92") (name "unconnected-(U$2-RTS-Pad14)") (class "Default")
      (node (ref "U$2") (pin "14") (pinfunction "RTS_14") (pintype "bidirectional"))
    )
    (net (code "93") (name "unconnected-(U$3-CTS-Pad9)") (class "Default")
      (node (ref "U$3") (pin "9") (pinfunction "CTS_9") (pintype "bidirectional"))
    )
    (net (code "94") (name "unconnected-(U$3-DCD-Pad12)") (class "Default")
      (node (ref "U$3") (pin "12") (pinfunction "DCD_12") (pintype "bidirectional"))
    )
    (net (code "95") (name "unconnected-(U$3-DSR-Pad10)") (class "Default")
      (node (ref "U$3") (pin "10") (pinfunction "DSR_10") (pintype "bidirectional"))
    )
    (net (code "96") (name "unconnected-(U$3-DTR-Pad13)") (class "Default")
      (node (ref "U$3") (pin "13") (pinfunction "DTR_13") (pintype "bidirectional"))
    )
    (net (code "97") (name "unconnected-(U$3-RI-Pad11)") (class "Default")
      (node (ref "U$3") (pin "11") (pinfunction "RI_11") (pintype "bidirectional"))
    )
    (net (code "98") (name "unconnected-(U$3-RS232-Pad15)") (class "Default")
      (node (ref "U$3") (pin "15") (pinfunction "RS232_15") (pintype "bidirectional"))
    )
    (net (code "99") (name "unconnected-(U$3-RTS-Pad14)") (class "Default")
      (node (ref "U$3") (pin "14") (pinfunction "RTS_14") (pintype "bidirectional"))
    )
    (net (code "100") (name "unconnected-(U1-PC0(ADC0)-Pad23)") (class "Default")
      (node (ref "U1") (pin "23") (pinfunction "PC0(ADC0)_23") (pintype "bidirectional"))
    )
  )
)
